# PiGRRL-ButtonPCB.net
KiCad netlist of a schematic drawn in EAGLE
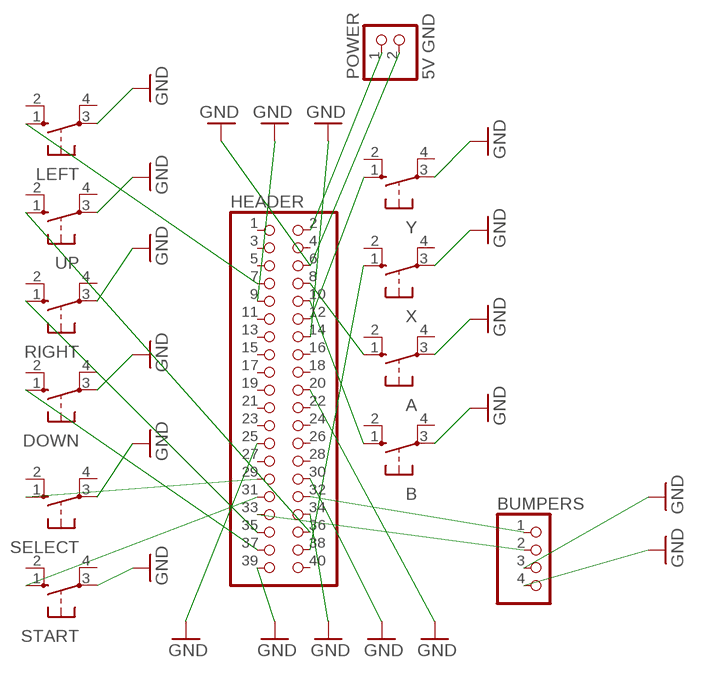
[diagram p0: schematic, sheet 1]

(export (version "E")
  (design (tool "Eeschema 10.0.6"))
  (components
    (comp (ref "A")
      (value "10-XX")
      (footprint "eagle-import:B3F-10XX")
      (fields (field (name "MPN") "B3F-1000"))
      (libsource (lib "eagle-import") (part "10-XX"))
    )
    (comp (ref "B")
      (value "10-XX")
      (footprint "eagle-import:B3F-10XX")
      (fields (field (name "MPN") "B3F-1000"))
      (libsource (lib "eagle-import") (part "10-XX"))
    )
    (comp (ref "BUMPERS")
      (value "PINHD-1X4")
      (footprint "eagle-import:1X04")
      (libsource (lib "eagle-import") (part "PINHD-1X4"))
    )
    (comp (ref "DOWN")
      (value "10-XX")
      (footprint "eagle-import:B3F-10XX")
      (fields (field (name "MPN") "B3F-1000"))
      (libsource (lib "eagle-import") (part "10-XX"))
    )
    (comp (ref "HEADER")
      (value "PINHD-2X20")
      (footprint "eagle-import:2X20")
      (libsource (lib "eagle-import") (part "PINHD-2X20"))
    )
    (comp (ref "LEFT")
      (value "10-XX")
      (footprint "eagle-import:B3F-10XX")
      (fields (field (name "MPN") "B3F-1000"))
      (libsource (lib "eagle-import") (part "10-XX"))
    )
    (comp (ref "POWER")
      (value "5V GND")
      (footprint "eagle-import:1X02")
      (libsource (lib "eagle-import") (part "PINHD-1X2"))
    )
    (comp (ref "RIGHT")
      (value "10-XX")
      (footprint "eagle-import:B3F-10XX")
      (fields (field (name "MPN") "B3F-1000"))
      (libsource (lib "eagle-import") (part "10-XX"))
    )
    (comp (ref "SELECT")
      (value "10-XX")
      (footprint "eagle-import:B3F-10XX")
      (fields (field (name "MPN") "B3F-1000"))
      (libsource (lib "eagle-import") (part "10-XX"))
    )
    (comp (ref "START")
      (value "10-XX")
      (footprint "eagle-import:B3F-10XX")
      (fields (field (name "MPN") "B3F-1000"))
      (libsource (lib "eagle-import") (part "10-XX"))
    )
    (comp (ref "UP")
      (value "10-XX")
      (footprint "eagle-import:B3F-10XX")
      (fields (field (name "MPN") "B3F-1000"))
      (libsource (lib "eagle-import") (part "10-XX"))
    )
    (comp (ref "X")
      (value "10-XX")
      (footprint "eagle-import:B3F-10XX")
      (fields (field (name "MPN") "B3F-1000"))
      (libsource (lib "eagle-import") (part "10-XX"))
    )
    (comp (ref "Y")
      (value "10-XX")
      (footprint "eagle-import:B3F-10XX")
      (fields (field (name "MPN") "B3F-1000"))
      (libsource (lib "eagle-import") (part "10-XX"))
    )
  )
  (nets
    (net (code "1") (name "GND") (class "Default")
      (node (ref "A") (pin "3") (pinfunction "P_3") (pintype "passive"))
      (node (ref "B") (pin "3") (pinfunction "P_3") (pintype "passive"))
      (node (ref "BUMPERS") (pin "3") (pinfunction "3_3") (pintype "passive"))
      (node (ref "BUMPERS") (pin "4") (pinfunction "4_4") (pintype "passive"))
      (node (ref "DOWN") (pin "3") (pinfunction "P_3") (pintype "passive"))
      (node (ref "HEADER") (pin "14") (pinfunction "14_14") (pintype "passive"))
      (node (ref "HEADER") (pin "20") (pinfunction "20_20") (pintype "passive"))
      (node (ref "HEADER") (pin "25") (pinfunction "25_25") (pintype "passive"))
      (node (ref "HEADER") (pin "30") (pinfunction "30_30") (pintype "passive"))
      (node (ref "HEADER") (pin "34") (pinfunction "34_34") (pintype "passive"))
      (node (ref "HEADER") (pin "39") (pinfunction "39_39") (pintype "passive"))
      (node (ref "HEADER") (pin "6") (pinfunction "6_6") (pintype "passive"))
      (node (ref "HEADER") (pin "9") (pinfunction "9_9") (pintype "passive"))
      (node (ref "LEFT") (pin "3") (pinfunction "P_3") (pintype "passive"))
      (node (ref "POWER") (pin "2") (pinfunction "2_2") (pintype "passive"))
      (node (ref "RIGHT") (pin "3") (pinfunction "P_3") (pintype "passive"))
      (node (ref "SELECT") (pin "3") (pinfunction "P_3") (pintype "passive"))
      (node (ref "START") (pin "3") (pinfunction "P_3") (pintype "passive"))
      (node (ref "UP") (pin "3") (pinfunction "P_3") (pintype "passive"))
      (node (ref "X") (pin "3") (pinfunction "P_3") (pintype "passive"))
      (node (ref "Y") (pin "3") (pinfunction "P_3") (pintype "passive"))
    )
    (net (code "2") (name "Net-(A-S)") (class "Default")
      (node (ref "A") (pin "1") (pinfunction "S_1") (pintype "passive"))
      (node (ref "HEADER") (pin "8") (pinfunction "8_8") (pintype "passive"))
    )
    (net (code "3") (name "Net-(B-S)") (class "Default")
      (node (ref "B") (pin "1") (pinfunction "S_1") (pintype "passive"))
      (node (ref "HEADER") (pin "10") (pinfunction "10_10") (pintype "passive"))
    )
    (net (code "4") (name "Net-(BUMPERS-Pad1)") (class "Default")
      (node (ref "BUMPERS") (pin "1") (pinfunction "1_1") (pintype "passive"))
      (node (ref "HEADER") (pin "32") (pinfunction "32_32") (pintype "passive"))
    )
    (net (code "5") (name "Net-(BUMPERS-Pad2)") (class "Default")
      (node (ref "BUMPERS") (pin "2") (pinfunction "2_2") (pintype "passive"))
      (node (ref "HEADER") (pin "33") (pinfunction "33_33") (pintype "passive"))
    )
    (net (code "6") (name "Net-(DOWN-S)") (class "Default")
      (node (ref "DOWN") (pin "1") (pinfunction "S_1") (pintype "passive"))
      (node (ref "HEADER") (pin "37") (pinfunction "37_37") (pintype "passive"))
    )
    (net (code "7") (name "Net-(HEADER-Pad2)") (class "Default")
      (node (ref "HEADER") (pin "2") (pinfunction "2_2") (pintype "passive"))
      (node (ref "POWER") (pin "1") (pinfunction "1_1") (pintype "passive"))
    )
    (net (code "8") (name "Net-(LEFT-S)") (class "Default")
      (node (ref "HEADER") (pin "7") (pinfunction "7_7") (pintype "passive"))
      (node (ref "LEFT") (pin "1") (pinfunction "S_1") (pintype "passive"))
    )
    (net (code "9") (name "Net-(RIGHT-S)") (class "Default")
      (node (ref "HEADER") (pin "35") (pinfunction "35_35") (pintype "passive"))
      (node (ref "RIGHT") (pin "1") (pinfunction "S_1") (pintype "passive"))
    )
    (net (code "10") (name "Net-(SELECT-S)") (class "Default")
      (node (ref "HEADER") (pin "29") (pinfunction "29_29") (pintype "passive"))
      (node (ref "SELECT") (pin "1") (pinfunction "S_1") (pintype "passive"))
    )
    (net (code "11") (name "Net-(START-S)") (class "Default")
      (node (ref "HEADER") (pin "31") (pinfunction "31_31") (pintype "passive"))
      (node (ref "START") (pin "1") (pinfunction "S_1") (pintype "passive"))
    )
    (net (code "12") (name "Net-(UP-S)") (class "Default")
      (node (ref "HEADER") (pin "36") (pinfunction "36_36") (pintype "passive"))
      (node (ref "UP") (pin "1") (pinfunction "S_1") (pintype "passive"))
    )
    (net (code "13") (name "Net-(X-S)") (class "Default")
      (node (ref "HEADER") (pin "38") (pinfunction "38_38") (pintype "passive"))
      (node (ref "X") (pin "1") (pinfunction "S_1") (pintype "passive"))
    )
    (net (code "14") (name "Net-(Y-S)") (class "Default")
      (node (ref "HEADER") (pin "12") (pinfunction "12_12") (pintype "passive"))
      (node (ref "Y") (pin "1") (pinfunction "S_1") (pintype "passive"))
    )
    (net (code "15") (name "unconnected-(A-P1-Pad4)") (class "Default")
      (node (ref "A") (pin "4") (pinfunction "P1_4") (pintype "passive"))
    )
    (net (code "16") (name "unconnected-(A-S1-Pad2)") (class "Default")
      (node (ref "A") (pin "2") (pinfunction "S1_2") (pintype "passive"))
    )
    (net (code "17") (name "unconnected-(B-P1-Pad4)") (class "Default")
      (node (ref "B") (pin "4") (pinfunction "P1_4") (pintype "passive"))
    )
    (net (code "18") (name "unconnected-(B-S1-Pad2)") (class "Default")
      (node (ref "B") (pin "2") (pinfunction "S1_2") (pintype "passive"))
    )
    (net (code "19") (name "unconnected-(DOWN-P1-Pad4)") (class "Default")
      (node (ref "DOWN") (pin "4") (pinfunction "P1_4") (pintype "passive"))
    )
    (net (code "20") (name "unconnected-(DOWN-S1-Pad2)") (class "Default")
      (node (ref "DOWN") (pin "2") (pinfunction "S1_2") (pintype "passive"))
    )
    (net (code "21") (name "unconnected-(HEADER-Pad1)") (class "Default")
      (node (ref "HEADER") (pin "1") (pinfunction "1_1") (pintype "passive"))
    )
    (net (code "22") (name "unconnected-(HEADER-Pad3)") (class "Default")
      (node (ref "HEADER") (pin "3") (pinfunction "3_3") (pintype "passive"))
    )
    (net (code "23") (name "unconnected-(HEADER-Pad4)") (class "Default")
      (node (ref "HEADER") (pin "4") (pinfunction "4_4") (pintype "passive"))
    )
    (net (code "24") (name "unconnected-(HEADER-Pad5)") (class "Default")
      (node (ref "HEADER") (pin "5") (pinfunction "5_5") (pintype "passive"))
    )
    (net (code "25") (name "unconnected-(HEADER-Pad11)") (class "Default")
      (node (ref "HEADER") (pin "11") (pinfunction "11_11") (pintype "passive"))
    )
    (net (code "26") (name "unconnected-(HEADER-Pad13)") (class "Default")
      (node (ref "HEADER") (pin "13") (pinfunction "13_13") (pintype "passive"))
    )
    (net (code "27") (name "unconnected-(HEADER-Pad15)") (class "Default")
      (node (ref "HEADER") (pin "15") (pinfunction "15_15") (pintype "passive"))
    )
    (net (code "28") (name "unconnected-(HEADER-Pad16)") (class "Default")
      (node (ref "HEADER") (pin "16") (pinfunction "16_16") (pintype "passive"))
    )
    (net (code "29") (name "unconnected-(HEADER-Pad17)") (class "Default")
      (node (ref "HEADER") (pin "17") (pinfunction "17_17") (pintype "passive"))
    )
    (net (code "30") (name "unconnected-(HEADER-Pad18)") (class "Default")
      (node (ref "HEADER") (pin "18") (pinfunction "18_18") (pintype "passive"))
    )
    (net (code "31") (name "unconnected-(HEADER-Pad19)") (class "Default")
      (node (ref "HEADER") (pin "19") (pinfunction "19_19") (pintype "passive"))
    )
    (net (code "32") (name "unconnected-(HEADER-Pad21)") (class "Default")
      (node (ref "HEADER") (pin "21") (pinfunction "21_21") (pintype "passive"))
    )
    (net (code "33") (name "unconnected-(HEADER-Pad22)") (class "Default")
      (node (ref "HEADER") (pin "22") (pinfunction "22_22") (pintype "passive"))
    )
    (net (code "34") (name "unconnected-(HEADER-Pad23)") (class "Default")
      (node (ref "HEADER") (pin "23") (pinfunction "23_23") (pintype "passive"))
    )
    (net (code "35") (name "unconnected-(HEADER-Pad24)") (class "Default")
      (node (ref "HEADER") (pin "24") (pinfunction "24_24") (pintype "passive"))
    )
    (net (code "36") (name "unconnected-(HEADER-Pad26)") (class "Default")
      (node (ref "HEADER") (pin "26") (pinfunction "26_26") (pintype "passive"))
    )
    (net (code "37") (name "unconnected-(HEADER-Pad27)") (class "Default")
      (node (ref "HEADER") (pin "27") (pinfunction "27_27") (pintype "passive"))
    )
    (net (code "38") (name "unconnected-(HEADER-Pad28)") (class "Default")
      (node (ref "HEADER") (pin "28") (pinfunction "28_28") (pintype "passive"))
    )
    (net (code "39") (name "unconnected-(HEADER-Pad40)") (class "Default")
      (node (ref "HEADER") (pin "40") (pinfunction "40_40") (pintype "passive"))
    )
    (net (code "40") (name "unconnected-(LEFT-P1-Pad4)") (class "Default")
      (node (ref "LEFT") (pin "4") (pinfunction "P1_4") (pintype "passive"))
    )
    (net (code "41") (name "unconnected-(LEFT-S1-Pad2)") (class "Default")
      (node (ref "LEFT") (pin "2") (pinfunction "S1_2") (pintype "passive"))
    )
    (net (code "42") (name "unconnected-(RIGHT-P1-Pad4)") (class "Default")
      (node (ref "RIGHT") (pin "4") (pinfunction "P1_4") (pintype "passive"))
    )
    (net (code "43") (name "unconnected-(RIGHT-S1-Pad2)") (class "Default")
      (node (ref "RIGHT") (pin "2") (pinfunction "S1_2") (pintype "passive"))
    )
    (net (code "44") (name "unconnected-(SELECT-P1-Pad4)") (class "Default")
      (node (ref "SELECT") (pin "4") (pinfunction "P1_4") (pintype "passive"))
    )
    (net (code "45") (name "unconnected-(SELECT-S1-Pad2)") (class "Default")
      (node (ref "SELECT") (pin "2") (pinfunction "S1_2") (pintype "passive"))
    )
    (net (code "46") (name "unconnected-(START-P1-Pad4)") (class "Default")
      (node (ref "START") (pin "4") (pinfunction "P1_4") (pintype "passive"))
    )
    (net (code "47") (name "unconnected-(START-S1-Pad2)") (class "Default")
      (node (ref "START") (pin "2") (pinfunction "S1_2") (pintype "passive"))
    )
    (net (code "48") (name "unconnected-(UP-P1-Pad4)") (class "Default")
      (node (ref "UP") (pin "4") (pinfunction "P1_4") (pintype "passive"))
    )
    (net (code "49") (name "unconnected-(UP-S1-Pad2)") (class "Default")
      (node (ref "UP") (pin "2") (pinfunction "S1_2") (pintype "passive"))
    )
    (net (code "50") (name "unconnected-(X-P1-Pad4)") (class "Default")
      (node (ref "X") (pin "4") (pinfunction "P1_4") (pintype "passive"))
    )
    (net (code "51") (name "unconnected-(X-S1-Pad2)") (class "Default")
      (node (ref "X") (pin "2") (pinfunction "S1_2") (pintype "passive"))
    )
    (net (code "52") (name "unconnected-(Y-P1-Pad4)") (class "Default")
      (node (ref "Y") (pin "4") (pinfunction "P1_4") (pintype "passive"))
    )
    (net (code "53") (name "unconnected-(Y-S1-Pad2)") (class "Default")
      (node (ref "Y") (pin "2") (pinfunction "S1_2") (pintype "passive"))
    )
  )
)
